# 20241011.net
KiCad netlist of a schematic drawn in Altium Designer
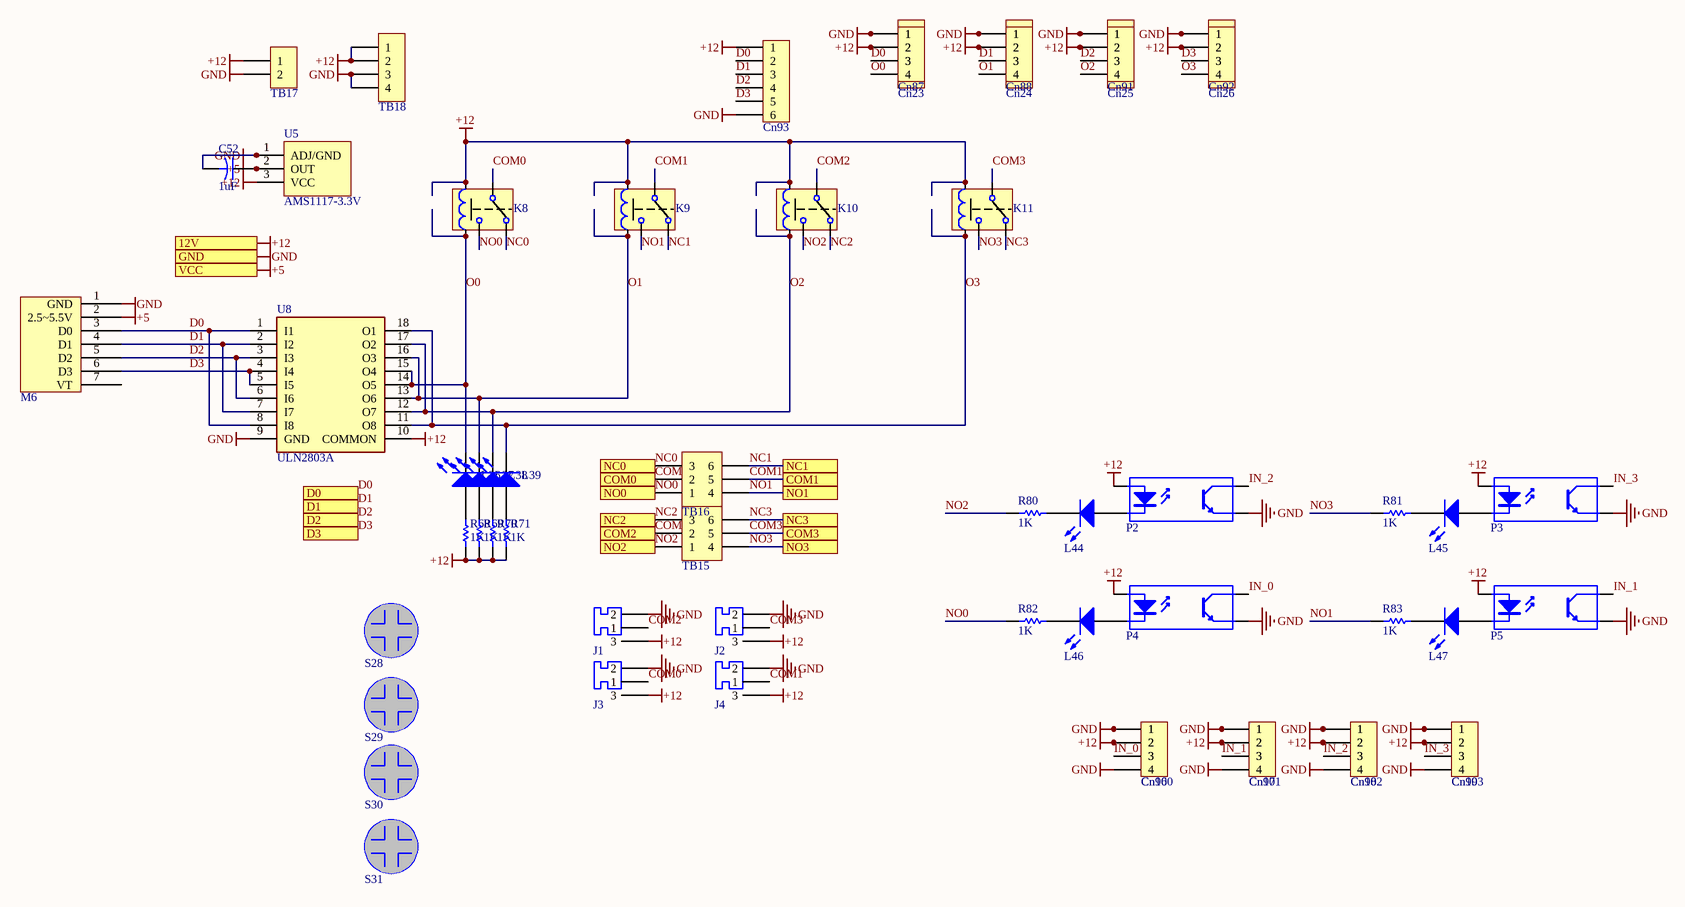
[diagram p0: 遙控繼電器_20241011.SchDoc]

(export (version "E")
  (design (tool "Eeschema 10.0.6"))
  (components
    (comp (ref "C52")
      (value "1uF")
      (footprint "CAP-1210")
      (description "電容")
      (libsource (lib "MyLibray") (part "Cap"))
    )
    (comp (ref "Cn23")
      (value "KF2510-4")
      (footprint "Connector_KF2510-4A")
      (description "接線端子")
      (libsource (lib "MyLibray") (part "Contact(4P)"))
    )
    (comp (ref "Cn24")
      (value "KF2510-4")
      (footprint "Connector_KF2510-4A")
      (description "接線端子")
      (libsource (lib "MyLibray") (part "Contact(4P)"))
    )
    (comp (ref "Cn25")
      (value "KF2510-4")
      (footprint "Connector_KF2510-4A")
      (description "接線端子")
      (libsource (lib "MyLibray") (part "Contact(4P)"))
    )
    (comp (ref "Cn26")
      (value "KF2510-4")
      (footprint "Connector_KF2510-4A")
      (description "接線端子")
      (libsource (lib "MyLibray") (part "Contact(4P)"))
    )
    (comp (ref "Cn87")
      (value "KF2510-3")
      (footprint "Connector_XH 2.54-3W")
      (description "連接器")
      (libsource (lib "MyLibray") (part "Conntact(3P)"))
    )
    (comp (ref "Cn88")
      (value "KF2510-3")
      (footprint "Connector_XH 2.54-3W")
      (description "連接器")
      (libsource (lib "MyLibray") (part "Conntact(3P)"))
    )
    (comp (ref "Cn91")
      (value "KF2510-3")
      (footprint "Connector_XH 2.54-3W")
      (description "連接器")
      (libsource (lib "MyLibray") (part "Conntact(3P)"))
    )
    (comp (ref "Cn92")
      (value "KF2510-3")
      (footprint "Connector_XH 2.54-3W")
      (description "連接器")
      (libsource (lib "MyLibray") (part "Conntact(3P)"))
    )
    (comp (ref "Cn93")
      (value "KF2510-6")
      (footprint "Connector_KF2510-6A")
      (description "連接器")
      (libsource (lib "MyLibray") (part "Conntact(6P)"))
    )
    (comp (ref "Cn96")
      (value "KF2510-3")
      (footprint "Connector_XH 2.54-3W")
      (description "連接器")
      (libsource (lib "MyLibray") (part "Conntact(3P)"))
    )
    (comp (ref "Cn97")
      (value "KF2510-3")
      (footprint "Connector_XH 2.54-3W")
      (description "連接器")
      (libsource (lib "MyLibray") (part "Conntact(3P)"))
    )
    (comp (ref "Cn98")
      (value "KF2510-3")
      (footprint "Connector_XH 2.54-3W")
      (description "連接器")
      (libsource (lib "MyLibray") (part "Conntact(3P)"))
    )
    (comp (ref "Cn99")
      (value "KF2510-3")
      (footprint "Connector_XH 2.54-3W")
      (description "連接器")
      (libsource (lib "MyLibray") (part "Conntact(3P)"))
    )
    (comp (ref "Cn100")
      (value "KF2510-4")
      (footprint "Connector_KF2510-4A")
      (description "連接器")
      (libsource (lib "MyLibray") (part "Conntact(4P)"))
    )
    (comp (ref "Cn101")
      (value "KF2510-4")
      (footprint "Connector_KF2510-4A")
      (description "連接器")
      (libsource (lib "MyLibray") (part "Conntact(4P)"))
    )
    (comp (ref "Cn102")
      (value "KF2510-4")
      (footprint "Connector_KF2510-4A")
      (description "連接器")
      (libsource (lib "MyLibray") (part "Conntact(4P)"))
    )
    (comp (ref "Cn103")
      (value "KF2510-4")
      (footprint "Connector_KF2510-4A")
      (description "連接器")
      (libsource (lib "MyLibray") (part "Conntact(4P)"))
    )
    (comp (ref "J1")
      (value "Jumper(3P)")
      (footprint "Bypass_Jumper(3P)")
      (description "跳線帽")
      (libsource (lib "MyLibray") (part "Bypass_Jumper(3P)"))
    )
    (comp (ref "J2")
      (value "Jumper(3P)")
      (footprint "Bypass_Jumper(3P)")
      (description "跳線帽")
      (libsource (lib "MyLibray") (part "Bypass_Jumper(3P)"))
    )
    (comp (ref "J3")
      (value "Jumper(3P)")
      (footprint "Bypass_Jumper(3P)")
      (description "跳線帽")
      (libsource (lib "MyLibray") (part "Bypass_Jumper(3P)"))
    )
    (comp (ref "J4")
      (value "Jumper(3P)")
      (footprint "Bypass_Jumper(3P)")
      (description "跳線帽")
      (libsource (lib "MyLibray") (part "Bypass_Jumper(3P)"))
    )
    (comp (ref "K8")
      (value "G2R-1-24VDC")
      (footprint "RELAY-HF41F-012-ZST")
      (description "繼電器")
      (libsource (lib "MyLibray") (part "Relay"))
    )
    (comp (ref "K9")
      (value "G2R-1-24VDC")
      (footprint "RELAY-HF41F-012-ZST")
      (description "繼電器")
      (libsource (lib "MyLibray") (part "Relay"))
    )
    (comp (ref "K10")
      (value "G2R-1-24VDC")
      (footprint "RELAY-HF41F-012-ZST")
      (description "繼電器")
      (libsource (lib "MyLibray") (part "Relay"))
    )
    (comp (ref "K11")
      (value "G2R-1-24VDC")
      (footprint "RELAY-HF41F-012-ZST")
      (description "繼電器")
      (libsource (lib "MyLibray") (part "Relay"))
    )
    (comp (ref "L36")
      (value "藍")
      (footprint "LED-1206")
      (description "LED")
      (libsource (lib "MyLibray") (part "LED"))
    )
    (comp (ref "L37")
      (value "藍")
      (footprint "LED-1206")
      (description "LED")
      (libsource (lib "MyLibray") (part "LED"))
    )
    (comp (ref "L38")
      (value "藍")
      (footprint "LED-1206")
      (description "LED")
      (libsource (lib "MyLibray") (part "LED"))
    )
    (comp (ref "L39")
      (value "藍")
      (footprint "LED-1206")
      (description "LED")
      (libsource (lib "MyLibray") (part "LED"))
    )
    (comp (ref "L44")
      (value "紅")
      (footprint "LED-1206")
      (description "LED")
      (libsource (lib "MyLibray") (part "LED"))
    )
    (comp (ref "L45")
      (value "紅")
      (footprint "LED-1206")
      (description "LED")
      (libsource (lib "MyLibray") (part "LED"))
    )
    (comp (ref "L46")
      (value "紅")
      (footprint "LED-1206")
      (description "LED")
      (libsource (lib "MyLibray") (part "LED"))
    )
    (comp (ref "L47")
      (value "紅")
      (footprint "LED-1206")
      (description "LED")
      (libsource (lib "MyLibray") (part "LED"))
    )
    (comp (ref "M6")
      (value "XR390")
      (footprint "XR390 Module")
      (description "遙控器模組")
      (libsource (lib "MyModule") (part "XR390"))
    )
    (comp (ref "P2")
      (value "PC817")
      (footprint "PC817")
      (description "光耦")
      (libsource (lib "MyLibray") (part "PC817"))
    )
    (comp (ref "P3")
      (value "PC817")
      (footprint "PC817")
      (description "光耦")
      (libsource (lib "MyLibray") (part "PC817"))
    )
    (comp (ref "P4")
      (value "PC817")
      (footprint "PC817")
      (description "光耦")
      (libsource (lib "MyLibray") (part "PC817"))
    )
    (comp (ref "P5")
      (value "PC817")
      (footprint "PC817")
      (description "光耦")
      (libsource (lib "MyLibray") (part "PC817"))
    )
    (comp (ref "R68")
      (value "1K")
      (footprint "Res-1206")
      (description "電阻")
      (libsource (lib "MyLibray") (part "Res"))
    )
    (comp (ref "R69")
      (value "1K")
      (footprint "Res-1206")
      (description "電阻")
      (libsource (lib "MyLibray") (part "Res"))
    )
    (comp (ref "R70")
      (value "1K")
      (footprint "Res-1206")
      (description "電阻")
      (libsource (lib "MyLibray") (part "Res"))
    )
    (comp (ref "R71")
      (value "1K")
      (footprint "Res-1206")
      (description "電阻")
      (libsource (lib "MyLibray") (part "Res"))
    )
    (comp (ref "R80")
      (value "1K")
      (footprint "Res-1206")
      (description "電阻")
      (libsource (lib "MyLibray") (part "Res"))
    )
    (comp (ref "R81")
      (value "1K")
      (footprint "Res-1206")
      (description "電阻")
      (libsource (lib "MyLibray") (part "Res"))
    )
    (comp (ref "R82")
      (value "1K")
      (footprint "Res-1206")
      (description "電阻")
      (libsource (lib "MyLibray") (part "Res"))
    )
    (comp (ref "R83")
      (value "1K")
      (footprint "Res-1206")
      (description "電阻")
      (libsource (lib "MyLibray") (part "Res"))
    )
    (comp (ref "S28")
      (value "M3")
      (footprint "Screw M3")
      (description "螺絲(非焊接元件)")
      (libsource (lib "MyLibray") (part "Screw"))
    )
    (comp (ref "S29")
      (value "M3")
      (footprint "Screw M3")
      (description "螺絲(非焊接元件)")
      (libsource (lib "MyLibray") (part "Screw"))
    )
    (comp (ref "S30")
      (value "M3")
      (footprint "Screw M3")
      (description "螺絲(非焊接元件)")
      (libsource (lib "MyLibray") (part "Screw"))
    )
    (comp (ref "S31")
      (value "M3")
      (footprint "Screw M3")
      (description "螺絲(非焊接元件)")
      (libsource (lib "MyLibray") (part "Screw"))
    )
    (comp (ref "TB15")
      (value "KF2EDGRT-5.08_6P")
      (footprint "Terminal block(KF2EDGRT-3.81_2*3P)")
      (description "端子台")
      (libsource (lib "MyLibray") (part "Terminal block(6P)"))
    )
    (comp (ref "TB16")
      (value "KF2EDGRT-5.08_6P")
      (footprint "Terminal block(KF2EDGRT-3.81_2*3P)")
      (description "端子台")
      (libsource (lib "MyLibray") (part "Terminal block(6P)"))
    )
    (comp (ref "TB17")
      (value "ZB25(2P)")
      (footprint "Terminal block(KF2EDGR-5.08 _2P)")
      (description "端子台")
      (libsource (lib "MyLibray") (part "Terminal block(2P)"))
    )
    (comp (ref "TB18")
      (value "KF2EDGRT-5.08_4P")
      (footprint "Terminal block(KF2EDGR-5.08 _4P)")
      (description "端子台")
      (libsource (lib "MyLibray") (part "Terminal block(4P)"))
    )
    (comp (ref "U5")
      (value "AMS1117-3.3V")
      (footprint "SOT 223")
      (description "降壓IC,LOD")
      (libsource (lib "MyLibray") (part "AMS1117"))
    )
    (comp (ref "U8")
      (value "ULN2803A")
      (footprint "DIP-18")
      (description "閘極驅動器 P型 50V 0.5A")
      (fields
        (field (name "MOUSER PART NUMBER") "757-TBD60183AFNGEL")
        (field (name "MANUFACTURER_PART_NUMBER") "TBD62083AFNG,EL")
      )
      (libsource (lib "MyLibray") (part "TBD62083A"))
    )
  )
  (nets
    (net (code "1") (name "+5") (class "Default")
      (node (ref "C52") (pin "1") (pinfunction "1_1") (pintype "passive"))
      (node (ref "M6") (pin "2") (pinfunction "2.5~5.5V_2") (pintype "passive"))
      (node (ref "U5") (pin "2") (pinfunction "OUT_2") (pintype "passive"))
    )
    (net (code "2") (name "+12") (class "Default")
      (node (ref "Cn100") (pin "2") (pinfunction "2_2") (pintype "passive"))
      (node (ref "Cn101") (pin "2") (pinfunction "2_2") (pintype "passive"))
      (node (ref "Cn102") (pin "2") (pinfunction "2_2") (pintype "passive"))
      (node (ref "Cn103") (pin "2") (pinfunction "2_2") (pintype "passive"))
      (node (ref "Cn23") (pin "2") (pinfunction "2_2") (pintype "passive"))
      (node (ref "Cn24") (pin "2") (pinfunction "2_2") (pintype "passive"))
      (node (ref "Cn25") (pin "2") (pinfunction "2_2") (pintype "passive"))
      (node (ref "Cn26") (pin "2") (pinfunction "2_2") (pintype "passive"))
      (node (ref "Cn87") (pin "2") (pinfunction "2_2") (pintype "passive"))
      (node (ref "Cn88") (pin "2") (pinfunction "2_2") (pintype "passive"))
      (node (ref "Cn91") (pin "2") (pinfunction "2_2") (pintype "passive"))
      (node (ref "Cn92") (pin "2") (pinfunction "2_2") (pintype "passive"))
      (node (ref "Cn93") (pin "1") (pinfunction "1_1") (pintype "passive"))
      (node (ref "Cn96") (pin "2") (pinfunction "2_2") (pintype "passive"))
      (node (ref "Cn97") (pin "2") (pinfunction "2_2") (pintype "passive"))
      (node (ref "Cn98") (pin "2") (pinfunction "2_2") (pintype "passive"))
      (node (ref "Cn99") (pin "2") (pinfunction "2_2") (pintype "passive"))
      (node (ref "J1") (pin "3") (pinfunction "3_3") (pintype "passive"))
      (node (ref "J2") (pin "3") (pinfunction "3_3") (pintype "passive"))
      (node (ref "J3") (pin "3") (pinfunction "3_3") (pintype "passive"))
      (node (ref "J4") (pin "3") (pinfunction "3_3") (pintype "passive"))
      (node (ref "K10") (pin "4") (pinfunction "A1_4") (pintype "passive"))
      (node (ref "K11") (pin "4") (pinfunction "A1_4") (pintype "passive"))
      (node (ref "K8") (pin "4") (pinfunction "A1_4") (pintype "passive"))
      (node (ref "K9") (pin "4") (pinfunction "A1_4") (pintype "passive"))
      (node (ref "P2") (pin "1") (pinfunction "A_1") (pintype "passive"))
      (node (ref "P3") (pin "1") (pinfunction "A_1") (pintype "passive"))
      (node (ref "P4") (pin "1") (pinfunction "A_1") (pintype "passive"))
      (node (ref "P5") (pin "1") (pinfunction "A_1") (pintype "passive"))
      (node (ref "R68") (pin "2") (pinfunction "2_2") (pintype "passive"))
      (node (ref "R69") (pin "2") (pinfunction "2_2") (pintype "passive"))
      (node (ref "R70") (pin "2") (pinfunction "2_2") (pintype "passive"))
      (node (ref "R71") (pin "2") (pinfunction "2_2") (pintype "passive"))
      (node (ref "TB17") (pin "1") (pinfunction "1_1") (pintype "passive"))
      (node (ref "TB18") (pin "1") (pinfunction "1_1") (pintype "passive"))
      (node (ref "TB18") (pin "2") (pinfunction "2_2") (pintype "passive"))
      (node (ref "U5") (pin "3") (pinfunction "VCC_3") (pintype "power_in"))
      (node (ref "U8") (pin "10") (pinfunction "COMMON_10") (pintype "passive"))
    )
    (net (code "3") (name "/COM0") (class "Default")
      (node (ref "J3") (pin "1") (pinfunction "1_1") (pintype "passive"))
      (node (ref "K8") (pin "1") (pinfunction "COM_1") (pintype "passive"))
      (node (ref "TB16") (pin "2") (pinfunction "2_2") (pintype "passive"))
    )
    (net (code "4") (name "/COM1") (class "Default")
      (node (ref "J4") (pin "1") (pinfunction "1_1") (pintype "passive"))
      (node (ref "K9") (pin "1") (pinfunction "COM_1") (pintype "passive"))
      (node (ref "TB16") (pin "5") (pinfunction "5_5") (pintype "passive"))
    )
    (net (code "5") (name "/COM2") (class "Default")
      (node (ref "J1") (pin "1") (pinfunction "1_1") (pintype "passive"))
      (node (ref "K10") (pin "1") (pinfunction "COM_1") (pintype "passive"))
      (node (ref "TB15") (pin "2") (pinfunction "2_2") (pintype "passive"))
    )
    (net (code "6") (name "/COM3") (class "Default")
      (node (ref "J2") (pin "1") (pinfunction "1_1") (pintype "passive"))
      (node (ref "K11") (pin "1") (pinfunction "COM_1") (pintype "passive"))
      (node (ref "TB15") (pin "5") (pinfunction "5_5") (pintype "passive"))
    )
    (net (code "7") (name "/D0") (class "Default")
      (node (ref "Cn23") (pin "3") (pinfunction "3_3") (pintype "passive"))
      (node (ref "Cn87") (pin "3") (pinfunction "3_3") (pintype "passive"))
      (node (ref "Cn93") (pin "2") (pinfunction "2_2") (pintype "passive"))
      (node (ref "M6") (pin "3") (pinfunction "D0_3") (pintype "passive"))
      (node (ref "U8") (pin "1") (pinfunction "I1_1") (pintype "passive"))
      (node (ref "U8") (pin "8") (pinfunction "I8_8") (pintype "passive"))
    )
    (net (code "8") (name "/D1") (class "Default")
      (node (ref "Cn24") (pin "3") (pinfunction "3_3") (pintype "passive"))
      (node (ref "Cn88") (pin "3") (pinfunction "3_3") (pintype "passive"))
      (node (ref "Cn93") (pin "3") (pinfunction "3_3") (pintype "passive"))
      (node (ref "M6") (pin "4") (pinfunction "D1_4") (pintype "passive"))
      (node (ref "U8") (pin "2") (pinfunction "I2_2") (pintype "passive"))
      (node (ref "U8") (pin "7") (pinfunction "I7_7") (pintype "passive"))
    )
    (net (code "9") (name "/D2") (class "Default")
      (node (ref "Cn25") (pin "3") (pinfunction "3_3") (pintype "passive"))
      (node (ref "Cn91") (pin "3") (pinfunction "3_3") (pintype "passive"))
      (node (ref "Cn93") (pin "4") (pinfunction "4_4") (pintype "passive"))
      (node (ref "M6") (pin "5") (pinfunction "D2_5") (pintype "passive"))
      (node (ref "U8") (pin "3") (pinfunction "I3_3") (pintype "passive"))
      (node (ref "U8") (pin "6") (pinfunction "I6_6") (pintype "passive"))
    )
    (net (code "10") (name "/D3") (class "Default")
      (node (ref "Cn26") (pin "3") (pinfunction "3_3") (pintype "passive"))
      (node (ref "Cn92") (pin "3") (pinfunction "3_3") (pintype "passive"))
      (node (ref "Cn93") (pin "5") (pinfunction "5_5") (pintype "passive"))
      (node (ref "M6") (pin "6") (pinfunction "D3_6") (pintype "passive"))
      (node (ref "U8") (pin "4") (pinfunction "I4_4") (pintype "passive"))
      (node (ref "U8") (pin "5") (pinfunction "I5_5") (pintype "passive"))
    )
    (net (code "11") (name "/IN_0") (class "Default")
      (node (ref "Cn100") (pin "3") (pinfunction "3_3") (pintype "passive"))
      (node (ref "Cn96") (pin "3") (pinfunction "3_3") (pintype "passive"))
      (node (ref "P4") (pin "4") (pinfunction "C_4") (pintype "passive"))
    )
    (net (code "12") (name "/IN_1") (class "Default")
      (node (ref "Cn101") (pin "3") (pinfunction "3_3") (pintype "passive"))
      (node (ref "Cn97") (pin "3") (pinfunction "3_3") (pintype "passive"))
      (node (ref "P5") (pin "4") (pinfunction "C_4") (pintype "passive"))
    )
    (net (code "13") (name "/IN_2") (class "Default")
      (node (ref "Cn102") (pin "3") (pinfunction "3_3") (pintype "passive"))
      (node (ref "Cn98") (pin "3") (pinfunction "3_3") (pintype "passive"))
      (node (ref "P2") (pin "4") (pinfunction "C_4") (pintype "passive"))
    )
    (net (code "14") (name "/IN_3") (class "Default")
      (node (ref "Cn103") (pin "3") (pinfunction "3_3") (pintype "passive"))
      (node (ref "Cn99") (pin "3") (pinfunction "3_3") (pintype "passive"))
      (node (ref "P3") (pin "4") (pinfunction "C_4") (pintype "passive"))
    )
    (net (code "15") (name "/NC0") (class "Default")
      (node (ref "K8") (pin "3") (pinfunction "NC_3") (pintype "passive"))
      (node (ref "TB16") (pin "3") (pinfunction "3_3") (pintype "passive"))
    )
    (net (code "16") (name "/NC1") (class "Default")
      (node (ref "K9") (pin "3") (pinfunction "NC_3") (pintype "passive"))
      (node (ref "TB16") (pin "6") (pinfunction "6_6") (pintype "passive"))
    )
    (net (code "17") (name "/NC2") (class "Default")
      (node (ref "K10") (pin "3") (pinfunction "NC_3") (pintype "passive"))
      (node (ref "TB15") (pin "3") (pinfunction "3_3") (pintype "passive"))
    )
    (net (code "18") (name "/NC3") (class "Default")
      (node (ref "K11") (pin "3") (pinfunction "NC_3") (pintype "passive"))
      (node (ref "TB15") (pin "6") (pinfunction "6_6") (pintype "passive"))
    )
    (net (code "19") (name "/NO0") (class "Default")
      (node (ref "K8") (pin "2") (pinfunction "NO_2") (pintype "passive"))
      (node (ref "R82") (pin "1") (pinfunction "1_1") (pintype "passive"))
      (node (ref "TB16") (pin "1") (pinfunction "1_1") (pintype "passive"))
    )
    (net (code "20") (name "/NO1") (class "Default")
      (node (ref "K9") (pin "2") (pinfunction "NO_2") (pintype "passive"))
      (node (ref "R83") (pin "1") (pinfunction "1_1") (pintype "passive"))
      (node (ref "TB16") (pin "4") (pinfunction "4_4") (pintype "passive"))
    )
    (net (code "21") (name "/NO2") (class "Default")
      (node (ref "K10") (pin "2") (pinfunction "NO_2") (pintype "passive"))
      (node (ref "R80") (pin "1") (pinfunction "1_1") (pintype "passive"))
      (node (ref "TB15") (pin "1") (pinfunction "1_1") (pintype "passive"))
    )
    (net (code "22") (name "/NO3") (class "Default")
      (node (ref "K11") (pin "2") (pinfunction "NO_2") (pintype "passive"))
      (node (ref "R81") (pin "1") (pinfunction "1_1") (pintype "passive"))
      (node (ref "TB15") (pin "4") (pinfunction "4_4") (pintype "passive"))
    )
    (net (code "23") (name "/O0") (class "Default")
      (node (ref "Cn23") (pin "4") (pinfunction "4_4") (pintype "passive"))
      (node (ref "K8") (pin "5") (pinfunction "A2_5") (pintype "passive"))
      (node (ref "L36") (pin "1") (pinfunction "K_1") (pintype "passive"))
      (node (ref "U8") (pin "14") (pinfunction "O5_14") (pintype "passive"))
      (node (ref "U8") (pin "15") (pinfunction "O4_15") (pintype "passive"))
    )
    (net (code "24") (name "/O1") (class "Default")
      (node (ref "Cn24") (pin "4") (pinfunction "4_4") (pintype "passive"))
      (node (ref "K9") (pin "5") (pinfunction "A2_5") (pintype "passive"))
      (node (ref "L37") (pin "1") (pinfunction "K_1") (pintype "passive"))
      (node (ref "U8") (pin "13") (pinfunction "O6_13") (pintype "passive"))
      (node (ref "U8") (pin "16") (pinfunction "O3_16") (pintype "passive"))
    )
    (net (code "25") (name "/O2") (class "Default")
      (node (ref "Cn25") (pin "4") (pinfunction "4_4") (pintype "passive"))
      (node (ref "K10") (pin "5") (pinfunction "A2_5") (pintype "passive"))
      (node (ref "L38") (pin "1") (pinfunction "K_1") (pintype "passive"))
      (node (ref "U8") (pin "12") (pinfunction "O7_12") (pintype "passive"))
      (node (ref "U8") (pin "17") (pinfunction "O2_17") (pintype "passive"))
    )
    (net (code "26") (name "/O3") (class "Default")
      (node (ref "Cn26") (pin "4") (pinfunction "4_4") (pintype "passive"))
      (node (ref "K11") (pin "5") (pinfunction "A2_5") (pintype "passive"))
      (node (ref "L39") (pin "1") (pinfunction "K_1") (pintype "passive"))
      (node (ref "U8") (pin "11") (pinfunction "O8_11") (pintype "passive"))
      (node (ref "U8") (pin "18") (pinfunction "O1_18") (pintype "passive"))
    )
    (net (code "27") (name "GND") (class "Default")
      (node (ref "C52") (pin "2") (pinfunction "2_2") (pintype "passive"))
      (node (ref "Cn100") (pin "1") (pinfunction "1_1") (pintype "passive"))
      (node (ref "Cn100") (pin "4") (pinfunction "4_4") (pintype "passive"))
      (node (ref "Cn101") (pin "1") (pinfunction "1_1") (pintype "passive"))
      (node (ref "Cn101") (pin "4") (pinfunction "4_4") (pintype "passive"))
      (node (ref "Cn102") (pin "1") (pinfunction "1_1") (pintype "passive"))
      (node (ref "Cn102") (pin "4") (pinfunction "4_4") (pintype "passive"))
      (node (ref "Cn103") (pin "1") (pinfunction "1_1") (pintype "passive"))
      (node (ref "Cn103") (pin "4") (pinfunction "4_4") (pintype "passive"))
      (node (ref "Cn23") (pin "1") (pinfunction "1_1") (pintype "passive"))
      (node (ref "Cn24") (pin "1") (pinfunction "1_1") (pintype "passive"))
      (node (ref "Cn25") (pin "1") (pinfunction "1_1") (pintype "passive"))
      (node (ref "Cn26") (pin "1") (pinfunction "1_1") (pintype "passive"))
      (node (ref "Cn87") (pin "1") (pinfunction "1_1") (pintype "passive"))
      (node (ref "Cn88") (pin "1") (pinfunction "1_1") (pintype "passive"))
      (node (ref "Cn91") (pin "1") (pinfunction "1_1") (pintype "passive"))
      (node (ref "Cn92") (pin "1") (pinfunction "1_1") (pintype "passive"))
      (node (ref "Cn93") (pin "6") (pinfunction "6_6") (pintype "passive"))
      (node (ref "Cn96") (pin "1") (pinfunction "1_1") (pintype "passive"))
      (node (ref "Cn97") (pin "1") (pinfunction "1_1") (pintype "passive"))
      (node (ref "Cn98") (pin "1") (pinfunction "1_1") (pintype "passive"))
      (node (ref "Cn99") (pin "1") (pinfunction "1_1") (pintype "passive"))
      (node (ref "J1") (pin "2") (pinfunction "2_2") (pintype "passive"))
      (node (ref "J2") (pin "2") (pinfunction "2_2") (pintype "passive"))
      (node (ref "J3") (pin "2") (pinfunction "2_2") (pintype "passive"))
      (node (ref "J4") (pin "2") (pinfunction "2_2") (pintype "passive"))
      (node (ref "M6") (pin "1") (pinfunction "GND_1") (pintype "passive"))
      (node (ref "P2") (pin "3") (pinfunction "E_3") (pintype "passive"))
      (node (ref "P3") (pin "3") (pinfunction "E_3") (pintype "passive"))
      (node (ref "P4") (pin "3") (pinfunction "E_3") (pintype "passive"))
      (node (ref "P5") (pin "3") (pinfunction "E_3") (pintype "passive"))
      (node (ref "TB17") (pin "2") (pinfunction "2_2") (pintype "passive"))
      (node (ref "TB18") (pin "3") (pinfunction "3_3") (pintype "passive"))
      (node (ref "TB18") (pin "4") (pinfunction "4_4") (pintype "passive"))
      (node (ref "U5") (pin "1") (pinfunction "ADJ/GND_1") (pintype "passive"))
      (node (ref "U8") (pin "9") (pinfunction "GND_9") (pintype "passive"))
    )
    (net (code "28") (name "Net-(L36-A)") (class "Default")
      (node (ref "L36") (pin "2") (pinfunction "A_2") (pintype "passive"))
      (node (ref "R68") (pin "1") (pinfunction "1_1") (pintype "passive"))
    )
    (net (code "29") (name "Net-(L37-A)") (class "Default")
      (node (ref "L37") (pin "2") (pinfunction "A_2") (pintype "passive"))
      (node (ref "R69") (pin "1") (pinfunction "1_1") (pintype "passive"))
    )
    (net (code "30") (name "Net-(L38-A)") (class "Default")
      (node (ref "L38") (pin "2") (pinfunction "A_2") (pintype "passive"))
      (node (ref "R70") (pin "1") (pinfunction "1_1") (pintype "passive"))
    )
    (net (code "31") (name "Net-(L39-A)") (class "Default")
      (node (ref "L39") (pin "2") (pinfunction "A_2") (pintype "passive"))
      (node (ref "R71") (pin "1") (pinfunction "1_1") (pintype "passive"))
    )
    (net (code "32") (name "Net-(L44-A)") (class "Default")
      (node (ref "L44") (pin "2") (pinfunction "A_2") (pintype "passive"))
      (node (ref "P2") (pin "2") (pinfunction "K_2") (pintype "passive"))
    )
    (net (code "33") (name "Net-(L44-K)") (class "Default")
      (node (ref "L44") (pin "1") (pinfunction "K_1") (pintype "passive"))
      (node (ref "R80") (pin "2") (pinfunction "2_2") (pintype "passive"))
    )
    (net (code "34") (name "Net-(L45-A)") (class "Default")
      (node (ref "L45") (pin "2") (pinfunction "A_2") (pintype "passive"))
      (node (ref "P3") (pin "2") (pinfunction "K_2") (pintype "passive"))
    )
    (net (code "35") (name "Net-(L45-K)") (class "Default")
      (node (ref "L45") (pin "1") (pinfunction "K_1") (pintype "passive"))
      (node (ref "R81") (pin "2") (pinfunction "2_2") (pintype "passive"))
    )
    (net (code "36") (name "Net-(L46-A)") (class "Default")
      (node (ref "L46") (pin "2") (pinfunction "A_2") (pintype "passive"))
      (node (ref "P4") (pin "2") (pinfunction "K_2") (pintype "passive"))
    )
    (net (code "37") (name "Net-(L46-K)") (class "Default")
      (node (ref "L46") (pin "1") (pinfunction "K_1") (pintype "passive"))
      (node (ref "R82") (pin "2") (pinfunction "2_2") (pintype "passive"))
    )
    (net (code "38") (name "Net-(L47-A)") (class "Default")
      (node (ref "L47") (pin "2") (pinfunction "A_2") (pintype "passive"))
      (node (ref "P5") (pin "2") (pinfunction "K_2") (pintype "passive"))
    )
    (net (code "39") (name "Net-(L47-K)") (class "Default")
      (node (ref "L47") (pin "1") (pinfunction "K_1") (pintype "passive"))
      (node (ref "R83") (pin "2") (pinfunction "2_2") (pintype "passive"))
    )
    (net (code "40") (name "unconnected-(M6-VT-Pad7)") (class "Default")
      (node (ref "M6") (pin "7") (pinfunction "VT_7") (pintype "passive"))
    )
  )
)
